# MainController.net
KiCad netlist of a schematic drawn in EAGLE
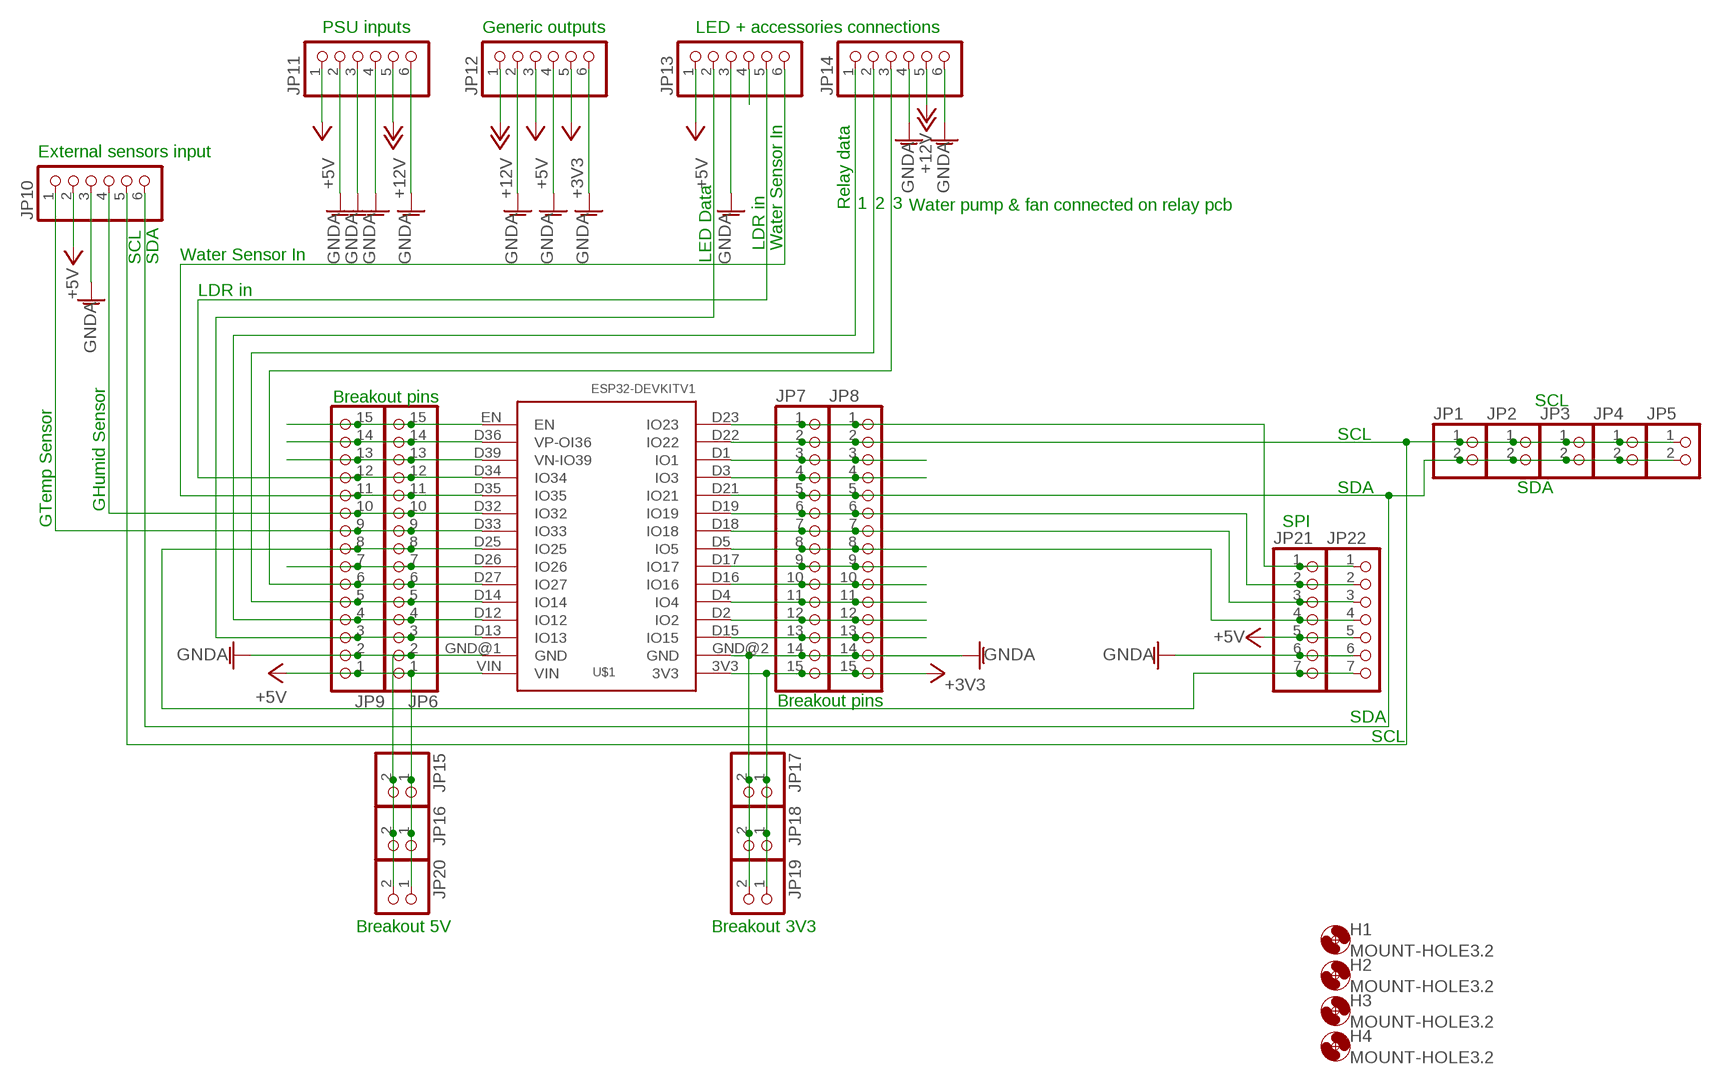
[diagram p0: schematic, sheet 1]

(export (version "E")
  (design (tool "Eeschema 10.0.6"))
  (components
    (comp (ref "H1")
      (value "MOUNT-HOLE3.2")
      (footprint "eagle-import:3,2")
      (libsource (lib "eagle-import") (part "MOUNT-HOLE3.2"))
    )
    (comp (ref "H2")
      (value "MOUNT-HOLE3.2")
      (footprint "eagle-import:3,2")
      (libsource (lib "eagle-import") (part "MOUNT-HOLE3.2"))
    )
    (comp (ref "H3")
      (value "MOUNT-HOLE3.2")
      (footprint "eagle-import:3,2")
      (libsource (lib "eagle-import") (part "MOUNT-HOLE3.2"))
    )
    (comp (ref "H4")
      (value "MOUNT-HOLE3.2")
      (footprint "eagle-import:3,2")
      (libsource (lib "eagle-import") (part "MOUNT-HOLE3.2"))
    )
    (comp (ref "JP1")
      (value "PINHD-1X2")
      (footprint "eagle-import:1X02")
      (libsource (lib "eagle-import") (part "PINHD-1X2"))
    )
    (comp (ref "JP2")
      (value "PINHD-1X2")
      (footprint "eagle-import:1X02")
      (libsource (lib "eagle-import") (part "PINHD-1X2"))
    )
    (comp (ref "JP3")
      (value "PINHD-1X2")
      (footprint "eagle-import:1X02")
      (libsource (lib "eagle-import") (part "PINHD-1X2"))
    )
    (comp (ref "JP4")
      (value "PINHD-1X2")
      (footprint "eagle-import:1X02")
      (libsource (lib "eagle-import") (part "PINHD-1X2"))
    )
    (comp (ref "JP5")
      (value "PINHD-1X2")
      (footprint "eagle-import:1X02")
      (libsource (lib "eagle-import") (part "PINHD-1X2"))
    )
    (comp (ref "JP6")
      (value "PINHD-1X15")
      (footprint "eagle-import:1X15")
      (libsource (lib "eagle-import") (part "PINHD-1X15"))
    )
    (comp (ref "JP7")
      (value "PINHD-1X15")
      (footprint "eagle-import:1X15")
      (libsource (lib "eagle-import") (part "PINHD-1X15"))
    )
    (comp (ref "JP8")
      (value "PINHD-1X15")
      (footprint "eagle-import:1X15")
      (libsource (lib "eagle-import") (part "PINHD-1X15"))
    )
    (comp (ref "JP9")
      (value "PINHD-1X15")
      (footprint "eagle-import:1X15")
      (libsource (lib "eagle-import") (part "PINHD-1X15"))
    )
    (comp (ref "JP10")
      (value "PINHD-1X6")
      (footprint "eagle-import:1X06")
      (libsource (lib "eagle-import") (part "PINHD-1X6"))
    )
    (comp (ref "JP11")
      (value "PINHD-1X6")
      (footprint "eagle-import:1X06")
      (libsource (lib "eagle-import") (part "PINHD-1X6"))
    )
    (comp (ref "JP12")
      (value "PINHD-1X6")
      (footprint "eagle-import:1X06")
      (libsource (lib "eagle-import") (part "PINHD-1X6"))
    )
    (comp (ref "JP13")
      (value "PINHD-1X6")
      (footprint "eagle-import:1X06")
      (libsource (lib "eagle-import") (part "PINHD-1X6"))
    )
    (comp (ref "JP14")
      (value "PINHD-1X6")
      (footprint "eagle-import:1X06")
      (libsource (lib "eagle-import") (part "PINHD-1X6"))
    )
    (comp (ref "JP15")
      (value "PINHD-1X2")
      (footprint "eagle-import:1X02")
      (libsource (lib "eagle-import") (part "PINHD-1X2"))
    )
    (comp (ref "JP16")
      (value "PINHD-1X2")
      (footprint "eagle-import:1X02")
      (libsource (lib "eagle-import") (part "PINHD-1X2"))
    )
    (comp (ref "JP17")
      (value "PINHD-1X2")
      (footprint "eagle-import:1X02")
      (libsource (lib "eagle-import") (part "PINHD-1X2"))
    )
    (comp (ref "JP18")
      (value "PINHD-1X2")
      (footprint "eagle-import:1X02")
      (libsource (lib "eagle-import") (part "PINHD-1X2"))
    )
    (comp (ref "JP19")
      (value "PINHD-1X2")
      (footprint "eagle-import:1X02")
      (libsource (lib "eagle-import") (part "PINHD-1X2"))
    )
    (comp (ref "JP20")
      (value "PINHD-1X2")
      (footprint "eagle-import:1X02")
      (libsource (lib "eagle-import") (part "PINHD-1X2"))
    )
    (comp (ref "JP21")
      (value "PINHD-1X7")
      (footprint "eagle-import:1X07")
      (libsource (lib "eagle-import") (part "PINHD-1X7"))
    )
    (comp (ref "JP22")
      (value "PINHD-1X7")
      (footprint "eagle-import:1X07")
      (libsource (lib "eagle-import") (part "PINHD-1X7"))
    )
    (comp (ref "U$1")
      (value "ESP32DEVKITV1")
      (footprint "eagle-import:ESP32-DEVKITV1")
      (libsource (lib "eagle-import") (part "ESP32DEVKITV1"))
    )
  )
  (nets
    (net (code "1") (name "+3V3") (class "Default")
      (node (ref "JP12") (pin "5") (pinfunction "5_5") (pintype "passive"))
      (node (ref "JP17") (pin "1") (pinfunction "1_1") (pintype "passive"))
      (node (ref "JP18") (pin "1") (pinfunction "1_1") (pintype "passive"))
      (node (ref "JP19") (pin "1") (pinfunction "1_1") (pintype "passive"))
      (node (ref "JP7") (pin "15") (pinfunction "15_15") (pintype "passive"))
      (node (ref "JP8") (pin "15") (pinfunction "15_15") (pintype "passive"))
      (node (ref "U$1") (pin "3V3") (pinfunction "3V3_3V3") (pintype "bidirectional"))
    )
    (net (code "2") (name "+5V") (class "Default")
      (node (ref "JP10") (pin "2") (pinfunction "2_2") (pintype "passive"))
      (node (ref "JP11") (pin "1") (pinfunction "1_1") (pintype "passive"))
      (node (ref "JP12") (pin "3") (pinfunction "3_3") (pintype "passive"))
      (node (ref "JP13") (pin "1") (pinfunction "1_1") (pintype "passive"))
      (node (ref "JP15") (pin "1") (pinfunction "1_1") (pintype "passive"))
      (node (ref "JP16") (pin "1") (pinfunction "1_1") (pintype "passive"))
      (node (ref "JP20") (pin "1") (pinfunction "1_1") (pintype "passive"))
      (node (ref "JP21") (pin "5") (pinfunction "5_5") (pintype "passive"))
      (node (ref "JP22") (pin "5") (pinfunction "5_5") (pintype "passive"))
      (node (ref "JP6") (pin "1") (pinfunction "1_1") (pintype "passive"))
      (node (ref "JP9") (pin "1") (pinfunction "1_1") (pintype "passive"))
      (node (ref "U$1") (pin "VIN") (pinfunction "VIN_VIN") (pintype "bidirectional"))
    )
    (net (code "3") (name "+12V") (class "Default")
      (node (ref "JP11") (pin "5") (pinfunction "5_5") (pintype "passive"))
      (node (ref "JP12") (pin "1") (pinfunction "1_1") (pintype "passive"))
      (node (ref "JP14") (pin "5") (pinfunction "5_5") (pintype "passive"))
    )
    (net (code "4") (name "GNDA") (class "Default")
      (node (ref "JP10") (pin "3") (pinfunction "3_3") (pintype "passive"))
      (node (ref "JP11") (pin "2") (pinfunction "2_2") (pintype "passive"))
      (node (ref "JP11") (pin "3") (pinfunction "3_3") (pintype "passive"))
      (node (ref "JP11") (pin "4") (pinfunction "4_4") (pintype "passive"))
      (node (ref "JP11") (pin "6") (pinfunction "6_6") (pintype "passive"))
      (node (ref "JP12") (pin "2") (pinfunction "2_2") (pintype "passive"))
      (node (ref "JP12") (pin "4") (pinfunction "4_4") (pintype "passive"))
      (node (ref "JP12") (pin "6") (pinfunction "6_6") (pintype "passive"))
      (node (ref "JP13") (pin "3") (pinfunction "3_3") (pintype "passive"))
      (node (ref "JP14") (pin "4") (pinfunction "4_4") (pintype "passive"))
      (node (ref "JP14") (pin "6") (pinfunction "6_6") (pintype "passive"))
      (node (ref "JP15") (pin "2") (pinfunction "2_2") (pintype "passive"))
      (node (ref "JP16") (pin "2") (pinfunction "2_2") (pintype "passive"))
      (node (ref "JP17") (pin "2") (pinfunction "2_2") (pintype "passive"))
      (node (ref "JP18") (pin "2") (pinfunction "2_2") (pintype "passive"))
      (node (ref "JP19") (pin "2") (pinfunction "2_2") (pintype "passive"))
      (node (ref "JP20") (pin "2") (pinfunction "2_2") (pintype "passive"))
      (node (ref "JP21") (pin "6") (pinfunction "6_6") (pintype "passive"))
      (node (ref "JP22") (pin "6") (pinfunction "6_6") (pintype "passive"))
      (node (ref "JP6") (pin "2") (pinfunction "2_2") (pintype "passive"))
      (node (ref "JP7") (pin "14") (pinfunction "14_14") (pintype "passive"))
      (node (ref "JP8") (pin "14") (pinfunction "14_14") (pintype "passive"))
      (node (ref "JP9") (pin "2") (pinfunction "2_2") (pintype "passive"))
      (node (ref "U$1") (pin "GND@1") (pinfunction "GND_GND@1") (pintype "bidirectional"))
      (node (ref "U$1") (pin "GND@2") (pinfunction "GND_GND@2") (pintype "bidirectional"))
    )
    (net (code "5") (name "Net-(JP6-Pad15)") (class "Default")
      (node (ref "JP6") (pin "15") (pinfunction "15_15") (pintype "passive"))
      (node (ref "JP9") (pin "15") (pinfunction "15_15") (pintype "passive"))
      (node (ref "U$1") (pin "EN") (pinfunction "EN_EN") (pintype "bidirectional"))
    )
    (net (code "6") (name "Net-(U$1-IO1)") (class "Default")
      (node (ref "JP7") (pin "3") (pinfunction "3_3") (pintype "passive"))
      (node (ref "JP8") (pin "3") (pinfunction "3_3") (pintype "passive"))
      (node (ref "U$1") (pin "D1") (pinfunction "IO1_D1") (pintype "bidirectional"))
    )
    (net (code "7") (name "Net-(U$1-IO2)") (class "Default")
      (node (ref "JP7") (pin "12") (pinfunction "12_12") (pintype "passive"))
      (node (ref "JP8") (pin "12") (pinfunction "12_12") (pintype "passive"))
      (node (ref "U$1") (pin "D2") (pinfunction "IO2_D2") (pintype "bidirectional"))
    )
    (net (code "8") (name "Net-(U$1-IO3)") (class "Default")
      (node (ref "JP7") (pin "4") (pinfunction "4_4") (pintype "passive"))
      (node (ref "JP8") (pin "4") (pinfunction "4_4") (pintype "passive"))
      (node (ref "U$1") (pin "D3") (pinfunction "IO3_D3") (pintype "bidirectional"))
    )
    (net (code "9") (name "Net-(U$1-IO4)") (class "Default")
      (node (ref "JP7") (pin "11") (pinfunction "11_11") (pintype "passive"))
      (node (ref "JP8") (pin "11") (pinfunction "11_11") (pintype "passive"))
      (node (ref "U$1") (pin "D4") (pinfunction "IO4_D4") (pintype "bidirectional"))
    )
    (net (code "10") (name "Net-(U$1-IO5)") (class "Default")
      (node (ref "JP21") (pin "4") (pinfunction "4_4") (pintype "passive"))
      (node (ref "JP22") (pin "4") (pinfunction "4_4") (pintype "passive"))
      (node (ref "JP7") (pin "8") (pinfunction "8_8") (pintype "passive"))
      (node (ref "JP8") (pin "8") (pinfunction "8_8") (pintype "passive"))
      (node (ref "U$1") (pin "D5") (pinfunction "IO5_D5") (pintype "bidirectional"))
    )
    (net (code "11") (name "Net-(U$1-IO12)") (class "Default")
      (node (ref "JP14") (pin "1") (pinfunction "1_1") (pintype "passive"))
      (node (ref "JP6") (pin "4") (pinfunction "4_4") (pintype "passive"))
      (node (ref "JP9") (pin "4") (pinfunction "4_4") (pintype "passive"))
      (node (ref "U$1") (pin "D12") (pinfunction "IO12_D12") (pintype "bidirectional"))
    )
    (net (code "12") (name "Net-(U$1-IO13)") (class "Default")
      (node (ref "JP13") (pin "2") (pinfunction "2_2") (pintype "passive"))
      (node (ref "JP6") (pin "3") (pinfunction "3_3") (pintype "passive"))
      (node (ref "JP9") (pin "3") (pinfunction "3_3") (pintype "passive"))
      (node (ref "U$1") (pin "D13") (pinfunction "IO13_D13") (pintype "bidirectional"))
    )
    (net (code "13") (name "Net-(U$1-IO14)") (class "Default")
      (node (ref "JP14") (pin "2") (pinfunction "2_2") (pintype "passive"))
      (node (ref "JP6") (pin "5") (pinfunction "5_5") (pintype "passive"))
      (node (ref "JP9") (pin "5") (pinfunction "5_5") (pintype "passive"))
      (node (ref "U$1") (pin "D14") (pinfunction "IO14_D14") (pintype "bidirectional"))
    )
    (net (code "14") (name "Net-(U$1-IO15)") (class "Default")
      (node (ref "JP7") (pin "13") (pinfunction "13_13") (pintype "passive"))
      (node (ref "JP8") (pin "13") (pinfunction "13_13") (pintype "passive"))
      (node (ref "U$1") (pin "D15") (pinfunction "IO15_D15") (pintype "bidirectional"))
    )
    (net (code "15") (name "Net-(U$1-IO16)") (class "Default")
      (node (ref "JP7") (pin "10") (pinfunction "10_10") (pintype "passive"))
      (node (ref "JP8") (pin "10") (pinfunction "10_10") (pintype "passive"))
      (node (ref "U$1") (pin "D16") (pinfunction "IO16_D16") (pintype "bidirectional"))
    )
    (net (code "16") (name "Net-(U$1-IO17)") (class "Default")
      (node (ref "JP7") (pin "9") (pinfunction "9_9") (pintype "passive"))
      (node (ref "JP8") (pin "9") (pinfunction "9_9") (pintype "passive"))
      (node (ref "U$1") (pin "D17") (pinfunction "IO17_D17") (pintype "bidirectional"))
    )
    (net (code "17") (name "Net-(U$1-IO18)") (class "Default")
      (node (ref "JP21") (pin "3") (pinfunction "3_3") (pintype "passive"))
      (node (ref "JP22") (pin "3") (pinfunction "3_3") (pintype "passive"))
      (node (ref "JP7") (pin "7") (pinfunction "7_7") (pintype "passive"))
      (node (ref "JP8") (pin "7") (pinfunction "7_7") (pintype "passive"))
      (node (ref "U$1") (pin "D18") (pinfunction "IO18_D18") (pintype "bidirectional"))
    )
    (net (code "18") (name "Net-(U$1-IO19)") (class "Default")
      (node (ref "JP21") (pin "2") (pinfunction "2_2") (pintype "passive"))
      (node (ref "JP22") (pin "2") (pinfunction "2_2") (pintype "passive"))
      (node (ref "JP7") (pin "6") (pinfunction "6_6") (pintype "passive"))
      (node (ref "JP8") (pin "6") (pinfunction "6_6") (pintype "passive"))
      (node (ref "U$1") (pin "D19") (pinfunction "IO19_D19") (pintype "bidirectional"))
    )
    (net (code "19") (name "Net-(U$1-IO21)") (class "Default")
      (node (ref "JP1") (pin "2") (pinfunction "2_2") (pintype "passive"))
      (node (ref "JP10") (pin "6") (pinfunction "6_6") (pintype "passive"))
      (node (ref "JP2") (pin "2") (pinfunction "2_2") (pintype "passive"))
      (node (ref "JP3") (pin "2") (pinfunction "2_2") (pintype "passive"))
      (node (ref "JP4") (pin "2") (pinfunction "2_2") (pintype "passive"))
      (node (ref "JP5") (pin "2") (pinfunction "2_2") (pintype "passive"))
      (node (ref "JP7") (pin "5") (pinfunction "5_5") (pintype "passive"))
      (node (ref "JP8") (pin "5") (pinfunction "5_5") (pintype "passive"))
      (node (ref "U$1") (pin "D21") (pinfunction "IO21_D21") (pintype "bidirectional"))
    )
    (net (code "20") (name "Net-(U$1-IO22)") (class "Default")
      (node (ref "JP1") (pin "1") (pinfunction "1_1") (pintype "passive"))
      (node (ref "JP10") (pin "5") (pinfunction "5_5") (pintype "passive"))
      (node (ref "JP2") (pin "1") (pinfunction "1_1") (pintype "passive"))
      (node (ref "JP3") (pin "1") (pinfunction "1_1") (pintype "passive"))
      (node (ref "JP4") (pin "1") (pinfunction "1_1") (pintype "passive"))
      (node (ref "JP5") (pin "1") (pinfunction "1_1") (pintype "passive"))
      (node (ref "JP7") (pin "2") (pinfunction "2_2") (pintype "passive"))
      (node (ref "JP8") (pin "2") (pinfunction "2_2") (pintype "passive"))
      (node (ref "U$1") (pin "D22") (pinfunction "IO22_D22") (pintype "bidirectional"))
    )
    (net (code "21") (name "Net-(U$1-IO23)") (class "Default")
      (node (ref "JP21") (pin "1") (pinfunction "1_1") (pintype "passive"))
      (node (ref "JP22") (pin "1") (pinfunction "1_1") (pintype "passive"))
      (node (ref "JP7") (pin "1") (pinfunction "1_1") (pintype "passive"))
      (node (ref "JP8") (pin "1") (pinfunction "1_1") (pintype "passive"))
      (node (ref "U$1") (pin "D23") (pinfunction "IO23_D23") (pintype "bidirectional"))
    )
    (net (code "22") (name "Net-(U$1-IO25)") (class "Default")
      (node (ref "JP21") (pin "7") (pinfunction "7_7") (pintype "passive"))
      (node (ref "JP22") (pin "7") (pinfunction "7_7") (pintype "passive"))
      (node (ref "JP6") (pin "8") (pinfunction "8_8") (pintype "passive"))
      (node (ref "JP9") (pin "8") (pinfunction "8_8") (pintype "passive"))
      (node (ref "U$1") (pin "D25") (pinfunction "IO25_D25") (pintype "bidirectional"))
    )
    (net (code "23") (name "Net-(U$1-IO26)") (class "Default")
      (node (ref "JP6") (pin "7") (pinfunction "7_7") (pintype "passive"))
      (node (ref "JP9") (pin "7") (pinfunction "7_7") (pintype "passive"))
      (node (ref "U$1") (pin "D26") (pinfunction "IO26_D26") (pintype "bidirectional"))
    )
    (net (code "24") (name "Net-(U$1-IO27)") (class "Default")
      (node (ref "JP14") (pin "3") (pinfunction "3_3") (pintype "passive"))
      (node (ref "JP6") (pin "6") (pinfunction "6_6") (pintype "passive"))
      (node (ref "JP9") (pin "6") (pinfunction "6_6") (pintype "passive"))
      (node (ref "U$1") (pin "D27") (pinfunction "IO27_D27") (pintype "bidirectional"))
    )
    (net (code "25") (name "Net-(U$1-IO32)") (class "Default")
      (node (ref "JP10") (pin "4") (pinfunction "4_4") (pintype "passive"))
      (node (ref "JP6") (pin "10") (pinfunction "10_10") (pintype "passive"))
      (node (ref "JP9") (pin "10") (pinfunction "10_10") (pintype "passive"))
      (node (ref "U$1") (pin "D32") (pinfunction "IO32_D32") (pintype "bidirectional"))
    )
    (net (code "26") (name "Net-(U$1-IO33)") (class "Default")
      (node (ref "JP10") (pin "1") (pinfunction "1_1") (pintype "passive"))
      (node (ref "JP6") (pin "9") (pinfunction "9_9") (pintype "passive"))
      (node (ref "JP9") (pin "9") (pinfunction "9_9") (pintype "passive"))
      (node (ref "U$1") (pin "D33") (pinfunction "IO33_D33") (pintype "bidirectional"))
    )
    (net (code "27") (name "Net-(U$1-IO34)") (class "Default")
      (node (ref "JP13") (pin "5") (pinfunction "5_5") (pintype "passive"))
      (node (ref "JP6") (pin "12") (pinfunction "12_12") (pintype "passive"))
      (node (ref "JP9") (pin "12") (pinfunction "12_12") (pintype "passive"))
      (node (ref "U$1") (pin "D34") (pinfunction "IO34_D34") (pintype "bidirectional"))
    )
    (net (code "28") (name "Net-(U$1-IO35)") (class "Default")
      (node (ref "JP13") (pin "6") (pinfunction "6_6") (pintype "passive"))
      (node (ref "JP6") (pin "11") (pinfunction "11_11") (pintype "passive"))
      (node (ref "JP9") (pin "11") (pinfunction "11_11") (pintype "passive"))
      (node (ref "U$1") (pin "D35") (pinfunction "IO35_D35") (pintype "bidirectional"))
    )
    (net (code "29") (name "Net-(U$1-VN-IO39)") (class "Default")
      (node (ref "JP6") (pin "13") (pinfunction "13_13") (pintype "passive"))
      (node (ref "JP9") (pin "13") (pinfunction "13_13") (pintype "passive"))
      (node (ref "U$1") (pin "D39") (pinfunction "VN-IO39_D39") (pintype "bidirectional"))
    )
    (net (code "30") (name "Net-(U$1-VP-OI36)") (class "Default")
      (node (ref "JP6") (pin "14") (pinfunction "14_14") (pintype "passive"))
      (node (ref "JP9") (pin "14") (pinfunction "14_14") (pintype "passive"))
      (node (ref "U$1") (pin "D36") (pinfunction "VP-OI36_D36") (pintype "bidirectional"))
    )
    (net (code "31") (name "unconnected-(JP13-Pad4)") (class "Default")
      (node (ref "JP13") (pin "4") (pinfunction "4_4") (pintype "passive"))
    )
  )
)
